# PiGateway2_2.net
KiCad netlist of a schematic drawn in EAGLE
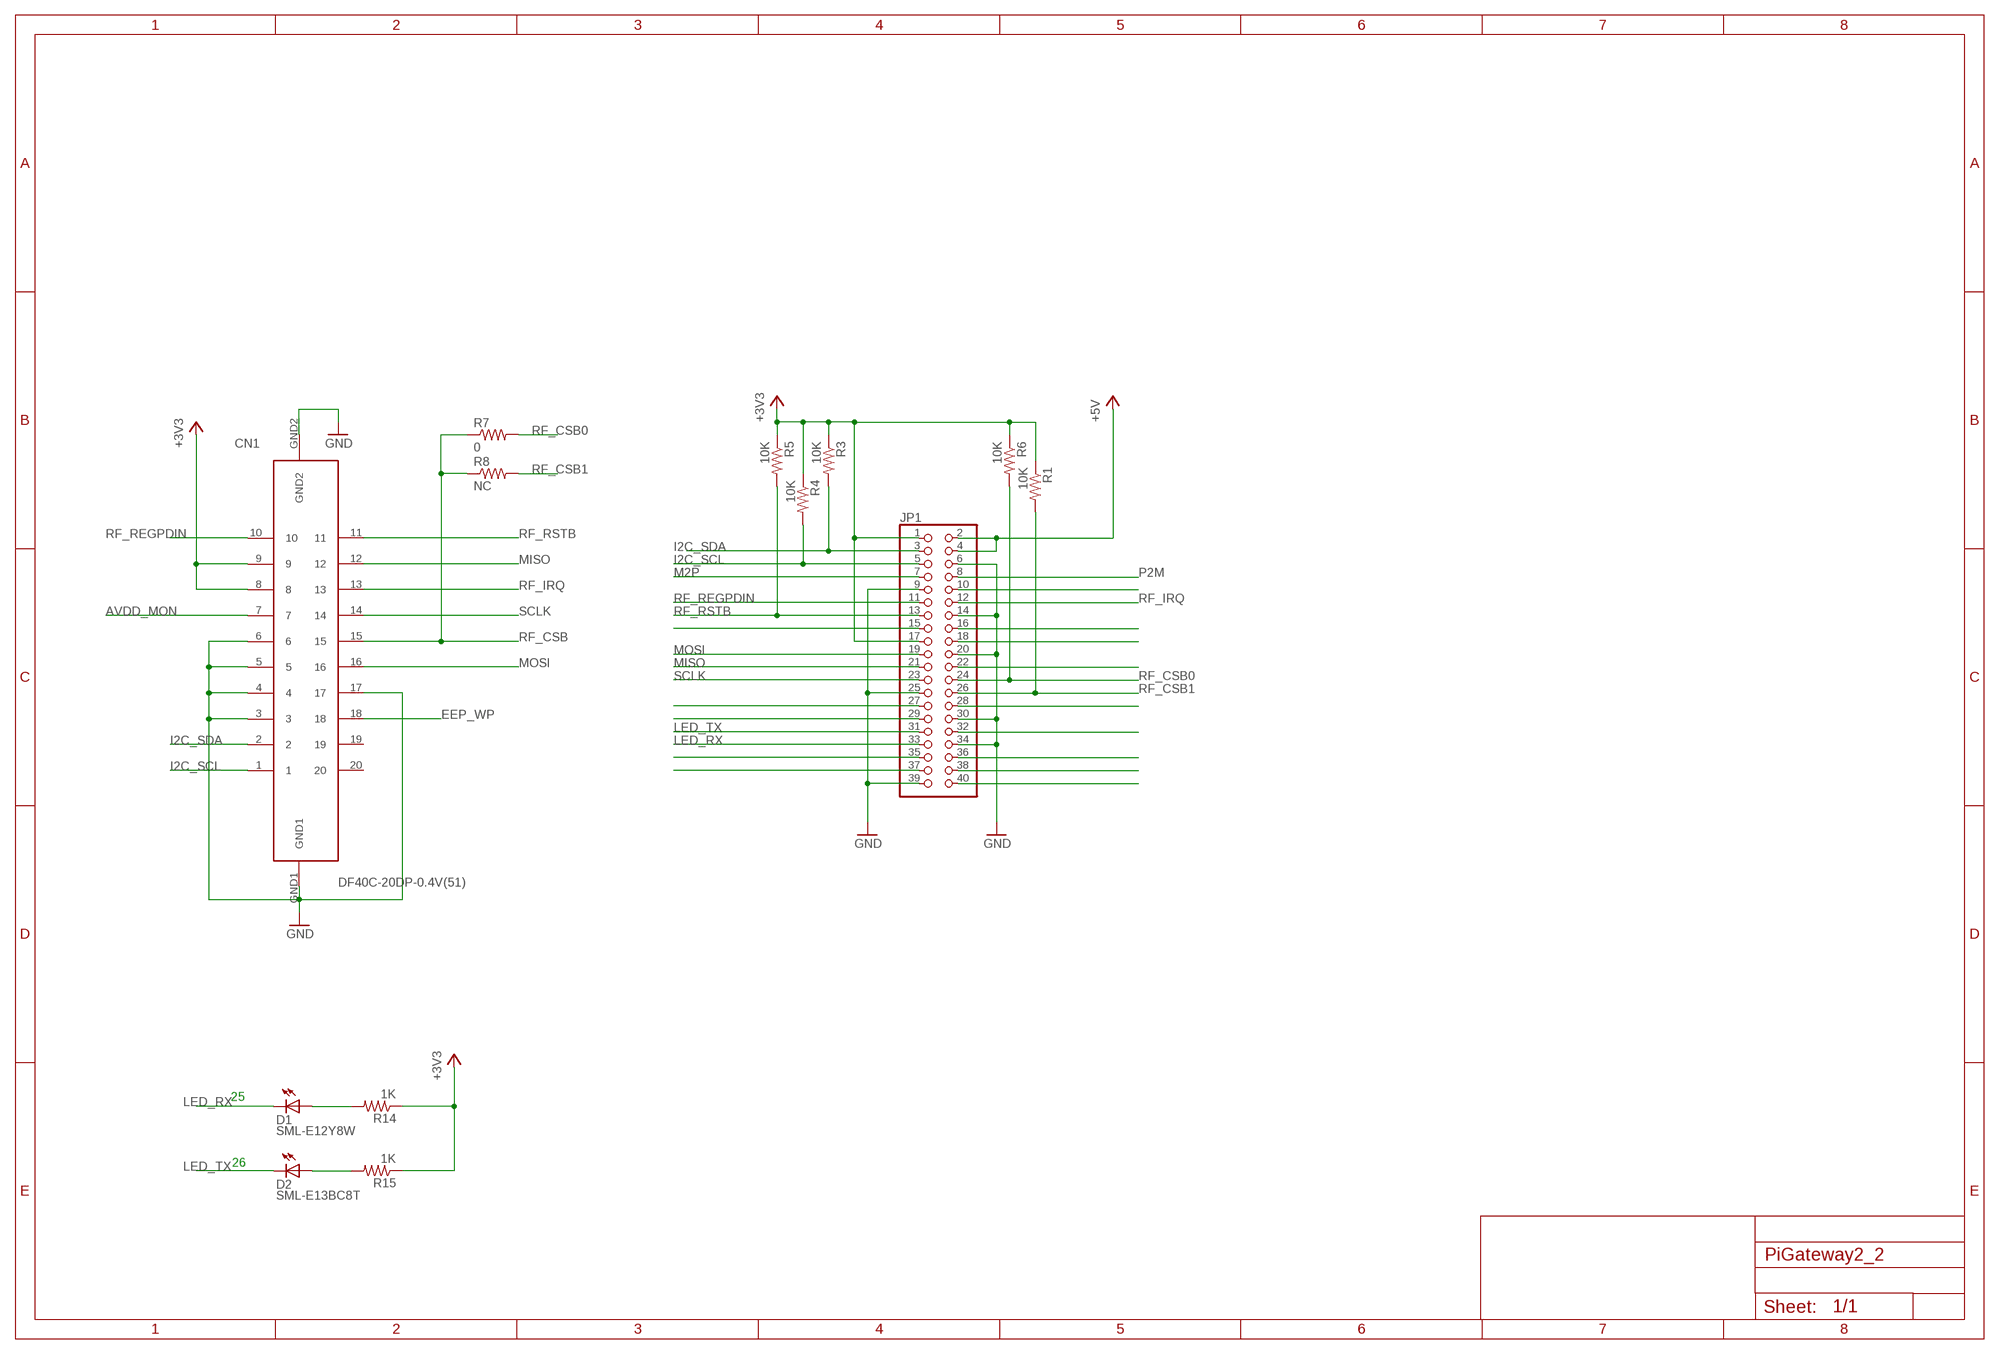
[diagram p0: schematic, sheet 1]

(export (version "E")
  (design (tool "Eeschema 10.0.6"))
  (components
    (comp (ref "CN1")
      (value "DF40C-20DP-0.4V(51)")
      (footprint "eagle-import:BP3596A")
      (libsource (lib "eagle-import") (part "BP3596A"))
    )
    (comp (ref "D1")
      (value "SML-E12Y8W")
      (footprint "eagle-import:SML-E1X")
      (libsource (lib "eagle-import") (part "SML-E1X"))
    )
    (comp (ref "D2")
      (value "SML-E13BC8T")
      (footprint "eagle-import:SML-E1X")
      (libsource (lib "eagle-import") (part "SML-E1X"))
    )
    (comp (ref "JP1")
      (value "PINHD-2X20")
      (footprint "eagle-import:2X20")
      (libsource (lib "eagle-import") (part "PINHD-2X20"))
    )
    (comp (ref "R1")
      (value "10K")
      (footprint "eagle-import:R0402")
      (libsource (lib "eagle-import") (part "R-US_R0402"))
    )
    (comp (ref "R3")
      (value "10K")
      (footprint "eagle-import:R0402")
      (libsource (lib "eagle-import") (part "R-US_R0402"))
    )
    (comp (ref "R4")
      (value "10K")
      (footprint "eagle-import:R0402")
      (libsource (lib "eagle-import") (part "R-US_R0402"))
    )
    (comp (ref "R5")
      (value "10K")
      (footprint "eagle-import:R0402")
      (libsource (lib "eagle-import") (part "R-US_R0402"))
    )
    (comp (ref "R6")
      (value "10K")
      (footprint "eagle-import:R0402")
      (libsource (lib "eagle-import") (part "R-US_R0402"))
    )
    (comp (ref "R7")
      (value "0")
      (footprint "eagle-import:R0402")
      (libsource (lib "eagle-import") (part "R-US_R0402"))
    )
    (comp (ref "R8")
      (value "NC")
      (footprint "eagle-import:R0402")
      (libsource (lib "eagle-import") (part "R-US_R0402"))
    )
    (comp (ref "R14")
      (value "1K")
      (footprint "eagle-import:R0402")
      (libsource (lib "eagle-import") (part "R-US_R0402"))
    )
    (comp (ref "R15")
      (value "1K")
      (footprint "eagle-import:R0402")
      (libsource (lib "eagle-import") (part "R-US_R0402"))
    )
  )
  (nets
    (net (code "1") (name "+3V3") (class "Default")
      (node (ref "CN1") (pin "8") (pinfunction "8_8") (pintype "bidirectional"))
      (node (ref "CN1") (pin "9") (pinfunction "9_9") (pintype "bidirectional"))
      (node (ref "JP1") (pin "1") (pinfunction "1_1") (pintype "passive"))
      (node (ref "JP1") (pin "17") (pinfunction "17_17") (pintype "passive"))
      (node (ref "R1") (pin "1") (pinfunction "1_1") (pintype "passive"))
      (node (ref "R14") (pin "1") (pinfunction "1_1") (pintype "passive"))
      (node (ref "R15") (pin "1") (pinfunction "1_1") (pintype "passive"))
      (node (ref "R3") (pin "1") (pinfunction "1_1") (pintype "passive"))
      (node (ref "R4") (pin "1") (pinfunction "1_1") (pintype "passive"))
      (node (ref "R5") (pin "1") (pinfunction "1_1") (pintype "passive"))
      (node (ref "R6") (pin "1") (pinfunction "1_1") (pintype "passive"))
    )
    (net (code "2") (name "+5V") (class "Default")
      (node (ref "JP1") (pin "2") (pinfunction "2_2") (pintype "passive"))
      (node (ref "JP1") (pin "4") (pinfunction "4_4") (pintype "passive"))
    )
    (net (code "3") (name "/AVDD_MON") (class "Default")
      (node (ref "CN1") (pin "7") (pinfunction "7_7") (pintype "bidirectional"))
    )
    (net (code "4") (name "/EEP_WP") (class "Default")
      (node (ref "CN1") (pin "18") (pinfunction "18_18") (pintype "bidirectional"))
    )
    (net (code "5") (name "/I2C_SCL") (class "Default")
      (node (ref "CN1") (pin "1") (pinfunction "1_1") (pintype "bidirectional"))
      (node (ref "JP1") (pin "5") (pinfunction "5_5") (pintype "passive"))
      (node (ref "R4") (pin "2") (pinfunction "2_2") (pintype "passive"))
    )
    (net (code "6") (name "/I2C_SDA") (class "Default")
      (node (ref "CN1") (pin "2") (pinfunction "2_2") (pintype "bidirectional"))
      (node (ref "JP1") (pin "3") (pinfunction "3_3") (pintype "passive"))
      (node (ref "R3") (pin "2") (pinfunction "2_2") (pintype "passive"))
    )
    (net (code "7") (name "/LED_RX") (class "Default")
      (node (ref "D1") (pin "C") (pinfunction "C_C") (pintype "passive"))
      (node (ref "JP1") (pin "33") (pinfunction "33_33") (pintype "passive"))
    )
    (net (code "8") (name "/LED_TX") (class "Default")
      (node (ref "D2") (pin "C") (pinfunction "C_C") (pintype "passive"))
      (node (ref "JP1") (pin "31") (pinfunction "31_31") (pintype "passive"))
    )
    (net (code "9") (name "/M2P") (class "Default")
      (node (ref "JP1") (pin "7") (pinfunction "7_7") (pintype "passive"))
    )
    (net (code "10") (name "/MISO") (class "Default")
      (node (ref "CN1") (pin "12") (pinfunction "12_12") (pintype "bidirectional"))
      (node (ref "JP1") (pin "21") (pinfunction "21_21") (pintype "passive"))
    )
    (net (code "11") (name "/MOSI") (class "Default")
      (node (ref "CN1") (pin "16") (pinfunction "16_16") (pintype "bidirectional"))
      (node (ref "JP1") (pin "19") (pinfunction "19_19") (pintype "passive"))
    )
    (net (code "12") (name "/P2M") (class "Default")
      (node (ref "JP1") (pin "8") (pinfunction "8_8") (pintype "passive"))
    )
    (net (code "13") (name "/RF_CSB") (class "Default")
      (node (ref "CN1") (pin "15") (pinfunction "15_15") (pintype "bidirectional"))
      (node (ref "R7") (pin "1") (pinfunction "1_1") (pintype "passive"))
      (node (ref "R8") (pin "1") (pinfunction "1_1") (pintype "passive"))
    )
    (net (code "14") (name "/RF_CSB0") (class "Default")
      (node (ref "JP1") (pin "24") (pinfunction "24_24") (pintype "passive"))
      (node (ref "R6") (pin "2") (pinfunction "2_2") (pintype "passive"))
      (node (ref "R7") (pin "2") (pinfunction "2_2") (pintype "passive"))
    )
    (net (code "15") (name "/RF_CSB1") (class "Default")
      (node (ref "JP1") (pin "26") (pinfunction "26_26") (pintype "passive"))
      (node (ref "R1") (pin "2") (pinfunction "2_2") (pintype "passive"))
      (node (ref "R8") (pin "2") (pinfunction "2_2") (pintype "passive"))
    )
    (net (code "16") (name "/RF_IRQ") (class "Default")
      (node (ref "CN1") (pin "13") (pinfunction "13_13") (pintype "bidirectional"))
      (node (ref "JP1") (pin "12") (pinfunction "12_12") (pintype "passive"))
    )
    (net (code "17") (name "/RF_REGPDIN") (class "Default")
      (node (ref "CN1") (pin "10") (pinfunction "10_10") (pintype "bidirectional"))
      (node (ref "JP1") (pin "11") (pinfunction "11_11") (pintype "passive"))
    )
    (net (code "18") (name "/RF_RSTB") (class "Default")
      (node (ref "CN1") (pin "11") (pinfunction "11_11") (pintype "bidirectional"))
      (node (ref "JP1") (pin "13") (pinfunction "13_13") (pintype "passive"))
      (node (ref "R5") (pin "2") (pinfunction "2_2") (pintype "passive"))
    )
    (net (code "19") (name "/SCLK") (class "Default")
      (node (ref "CN1") (pin "14") (pinfunction "14_14") (pintype "bidirectional"))
      (node (ref "JP1") (pin "23") (pinfunction "23_23") (pintype "passive"))
    )
    (net (code "20") (name "GND") (class "Default")
      (node (ref "CN1") (pin "17") (pinfunction "17_17") (pintype "bidirectional"))
      (node (ref "CN1") (pin "3") (pinfunction "3_3") (pintype "bidirectional"))
      (node (ref "CN1") (pin "4") (pinfunction "4_4") (pintype "bidirectional"))
      (node (ref "CN1") (pin "5") (pinfunction "5_5") (pintype "bidirectional"))
      (node (ref "CN1") (pin "6") (pinfunction "6_6") (pintype "bidirectional"))
      (node (ref "CN1") (pin "GND1") (pinfunction "GND1_GND1") (pintype "bidirectional"))
      (node (ref "CN1") (pin "GND2") (pinfunction "GND2_GND2") (pintype "bidirectional"))
      (node (ref "JP1") (pin "14") (pinfunction "14_14") (pintype "passive"))
      (node (ref "JP1") (pin "20") (pinfunction "20_20") (pintype "passive"))
      (node (ref "JP1") (pin "25") (pinfunction "25_25") (pintype "passive"))
      (node (ref "JP1") (pin "30") (pinfunction "30_30") (pintype "passive"))
      (node (ref "JP1") (pin "34") (pinfunction "34_34") (pintype "passive"))
      (node (ref "JP1") (pin "39") (pinfunction "39_39") (pintype "passive"))
      (node (ref "JP1") (pin "6") (pinfunction "6_6") (pintype "passive"))
      (node (ref "JP1") (pin "9") (pinfunction "9_9") (pintype "passive"))
    )
    (net (code "21") (name "Net-(D1-PadA)") (class "Default")
      (node (ref "D1") (pin "A") (pinfunction "A_A") (pintype "passive"))
      (node (ref "R14") (pin "2") (pinfunction "2_2") (pintype "passive"))
    )
    (net (code "22") (name "Net-(D2-PadA)") (class "Default")
      (node (ref "D2") (pin "A") (pinfunction "A_A") (pintype "passive"))
      (node (ref "R15") (pin "2") (pinfunction "2_2") (pintype "passive"))
    )
    (net (code "23") (name "unconnected-(CN1-Pad19)") (class "Default")
      (node (ref "CN1") (pin "19") (pinfunction "19_19") (pintype "bidirectional"))
    )
    (net (code "24") (name "unconnected-(CN1-Pad20)") (class "Default")
      (node (ref "CN1") (pin "20") (pinfunction "20_20") (pintype "bidirectional"))
    )
    (net (code "25") (name "unconnected-(JP1-Pad10)") (class "Default")
      (node (ref "JP1") (pin "10") (pinfunction "10_10") (pintype "passive"))
    )
    (net (code "26") (name "unconnected-(JP1-Pad15)") (class "Default")
      (node (ref "JP1") (pin "15") (pinfunction "15_15") (pintype "passive"))
    )
    (net (code "27") (name "unconnected-(JP1-Pad16)") (class "Default")
      (node (ref "JP1") (pin "16") (pinfunction "16_16") (pintype "passive"))
    )
    (net (code "28") (name "unconnected-(JP1-Pad18)") (class "Default")
      (node (ref "JP1") (pin "18") (pinfunction "18_18") (pintype "passive"))
    )
    (net (code "29") (name "unconnected-(JP1-Pad22)") (class "Default")
      (node (ref "JP1") (pin "22") (pinfunction "22_22") (pintype "passive"))
    )
    (net (code "30") (name "unconnected-(JP1-Pad27)") (class "Default")
      (node (ref "JP1") (pin "27") (pinfunction "27_27") (pintype "passive"))
    )
    (net (code "31") (name "unconnected-(JP1-Pad28)") (class "Default")
      (node (ref "JP1") (pin "28") (pinfunction "28_28") (pintype "passive"))
    )
    (net (code "32") (name "unconnected-(JP1-Pad29)") (class "Default")
      (node (ref "JP1") (pin "29") (pinfunction "29_29") (pintype "passive"))
    )
    (net (code "33") (name "unconnected-(JP1-Pad32)") (class "Default")
      (node (ref "JP1") (pin "32") (pinfunction "32_32") (pintype "passive"))
    )
    (net (code "34") (name "unconnected-(JP1-Pad35)") (class "Default")
      (node (ref "JP1") (pin "35") (pinfunction "35_35") (pintype "passive"))
    )
    (net (code "35") (name "unconnected-(JP1-Pad36)") (class "Default")
      (node (ref "JP1") (pin "36") (pinfunction "36_36") (pintype "passive"))
    )
    (net (code "36") (name "unconnected-(JP1-Pad37)") (class "Default")
      (node (ref "JP1") (pin "37") (pinfunction "37_37") (pintype "passive"))
    )
    (net (code "37") (name "unconnected-(JP1-Pad38)") (class "Default")
      (node (ref "JP1") (pin "38") (pinfunction "38_38") (pintype "passive"))
    )
    (net (code "38") (name "unconnected-(JP1-Pad40)") (class "Default")
      (node (ref "JP1") (pin "40") (pinfunction "40_40") (pintype "passive"))
    )
  )
)
